# mcu.net
KiCad netlist of a schematic drawn in Altium Designer
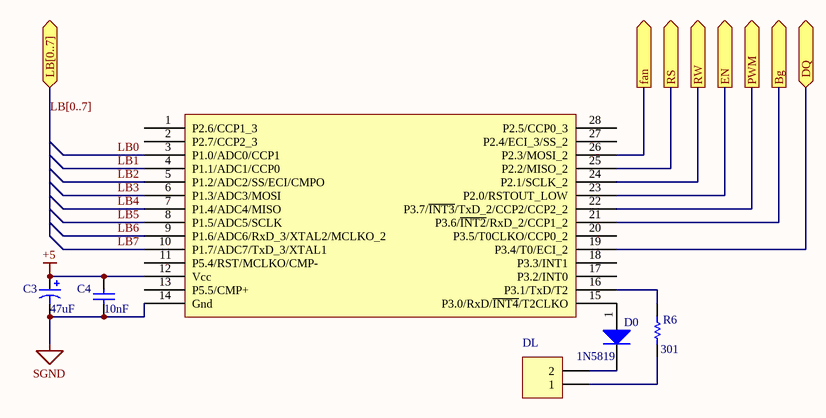
[diagram p0: mcu.SchDoc]

(export (version "E")
  (design (tool "Eeschema 10.0.6"))
  (components
    (comp (ref "C3")
      (value "47uF")
      (footprint "25V47uF(DIP)")
      (description "极性电容")
      (fields (field (name "Comment") "Cap1"))
      (libsource (lib "Self Establish") (part "Cap1"))
    )
    (comp (ref "C4")
      (value "10nF")
      (footprint "0805(M)")
      (description "非极性电容")
      (fields (field (name "Comment") "Cap2"))
      (libsource (lib "Self Establish") (part "Cap2"))
    )
    (comp (ref "D0")
      (value "1N5819")
      (footprint "SMA(M)")
      (description "肖特基二极管")
      (libsource (lib "Self Establish") (part "Diode2"))
    )
    (comp (ref "DL") (value "2Pin") (footprint "2Pin(DIP)") (libsource (lib "Self Establish") (part "2Pin")))
    (comp (ref "R6")
      (value "301")
      (footprint "0805(M)")
      (fields (field (name "Comment") "Res"))
      (libsource (lib "Self Establish") (part "Res"))
    )
    (comp (ref "U0")
      (value "STC15W401AS_SOP28_TSSOP28_SKDIP28")
      (footprint "SOP28")
      (libsource (lib "Self Establish") (part "STC15W401AS_SOP28_TSSOP28_SKDIP28"))
    )
  )
  (nets
    (net (code "1") (name "+5") (class "Default")
      (node (ref "C3") (pin "1") (pinfunction "1_1") (pintype "passive"))
      (node (ref "C4") (pin "2") (pinfunction "2_2") (pintype "passive"))
      (node (ref "U0") (pin "12") (pinfunction "Vcc_12") (pintype "passive"))
    )
    (net (code "2") (name "/Bg") (class "Default")
      (node (ref "U0") (pin "21") (pinfunction "P3.6/~{INT2}/RxD_2/CCP1_2_21") (pintype "passive"))
    )
    (net (code "3") (name "/DQ") (class "Default")
      (node (ref "U0") (pin "19") (pinfunction "P3.4/T0/ECI_2_19") (pintype "passive"))
    )
    (net (code "4") (name "/EN") (class "Default")
      (node (ref "U0") (pin "23") (pinfunction "P2.0/RSTOUT_LOW_23") (pintype "passive"))
    )
    (net (code "5") (name "/LB0") (class "Default")
      (node (ref "U0") (pin "3") (pinfunction "P1.0/ADC0/CCP1_3") (pintype "passive"))
    )
    (net (code "6") (name "/LB1") (class "Default")
      (node (ref "U0") (pin "4") (pinfunction "P1.1/ADC1/CCP0_4") (pintype "passive"))
    )
    (net (code "7") (name "/LB2") (class "Default")
      (node (ref "U0") (pin "5") (pinfunction "P1.2/ADC2/SS/ECI/CMPO_5") (pintype "passive"))
    )
    (net (code "8") (name "/LB3") (class "Default")
      (node (ref "U0") (pin "6") (pinfunction "P1.3/ADC3/MOSI_6") (pintype "passive"))
    )
    (net (code "9") (name "/LB4") (class "Default")
      (node (ref "U0") (pin "7") (pinfunction "P1.4/ADC4/MISO_7") (pintype "passive"))
    )
    (net (code "10") (name "/LB5") (class "Default")
      (node (ref "U0") (pin "8") (pinfunction "P1.5/ADC5/SCLK_8") (pintype "passive"))
    )
    (net (code "11") (name "/LB6") (class "Default")
      (node (ref "U0") (pin "9") (pinfunction "P1.6/ADC6/RxD_3/XTAL2/MCLKO_2_9") (pintype "passive"))
    )
    (net (code "12") (name "/LB7") (class "Default")
      (node (ref "U0") (pin "10") (pinfunction "P1.7/ADC7/TxD_3/XTAL1_10") (pintype "passive"))
    )
    (net (code "14") (name "/PWM") (class "Default")
      (node (ref "U0") (pin "22") (pinfunction "P3.7/~{INT3}/TxD_2/CCP2/CCP2_2_22") (pintype "passive"))
    )
    (net (code "15") (name "/RS") (class "Default")
      (node (ref "U0") (pin "25") (pinfunction "P2.2/MISO_2_25") (pintype "passive"))
    )
    (net (code "16") (name "/RW") (class "Default")
      (node (ref "U0") (pin "24") (pinfunction "P2.1/SCLK_2_24") (pintype "passive"))
    )
    (net (code "17") (name "/fan") (class "Default")
      (node (ref "U0") (pin "26") (pinfunction "P2.3/MOSI_2_26") (pintype "passive"))
    )
    (net (code "18") (name "Net-(D0-N)") (class "Default")
      (node (ref "D0") (pin "2") (pinfunction "N_2") (pintype "passive"))
      (node (ref "DL") (pin "2") (pinfunction "2_2") (pintype "passive"))
    )
    (net (code "19") (name "Net-(D0-P)") (class "Default")
      (node (ref "D0") (pin "1") (pinfunction "P_1") (pintype "passive"))
      (node (ref "U0") (pin "15") (pinfunction "P3.0/RxD/~{INT4}/T2CLKO_15") (pintype "passive"))
    )
    (net (code "20") (name "Net-(DL-Pad1)") (class "Default")
      (node (ref "DL") (pin "1") (pinfunction "1_1") (pintype "passive"))
      (node (ref "R6") (pin "2") (pinfunction "2_2") (pintype "passive"))
    )
    (net (code "21") (name "Net-(U0-P3.1{slash}TxD{slash}T2)") (class "Default")
      (node (ref "R6") (pin "1") (pinfunction "1_1") (pintype "passive"))
      (node (ref "U0") (pin "16") (pinfunction "P3.1/TxD/T2_16") (pintype "passive"))
    )
    (net (code "22") (name "SGND") (class "Default")
      (node (ref "C3") (pin "2") (pinfunction "2_2") (pintype "passive"))
      (node (ref "C4") (pin "1") (pinfunction "1_1") (pintype "passive"))
      (node (ref "U0") (pin "14") (pinfunction "Gnd_14") (pintype "passive"))
    )
    (net (code "23") (name "unconnected-(U0-P2.4{slash}ECI_3{slash}SS_2-Pad27)") (class "Default")
      (node (ref "U0") (pin "27") (pinfunction "P2.4/ECI_3/SS_2_27") (pintype "passive"))
    )
    (net (code "24") (name "unconnected-(U0-P2.5{slash}CCP0_3-Pad28)") (class "Default")
      (node (ref "U0") (pin "28") (pinfunction "P2.5/CCP0_3_28") (pintype "passive"))
    )
    (net (code "25") (name "unconnected-(U0-P2.6{slash}CCP1_3-Pad1)") (class "Default")
      (node (ref "U0") (pin "1") (pinfunction "P2.6/CCP1_3_1") (pintype "passive"))
    )
    (net (code "26") (name "unconnected-(U0-P2.7{slash}CCP2_3-Pad2)") (class "Default")
      (node (ref "U0") (pin "2") (pinfunction "P2.7/CCP2_3_2") (pintype "passive"))
    )
    (net (code "27") (name "unconnected-(U0-P3.2{slash}INT0-Pad17)") (class "Default")
      (node (ref "U0") (pin "17") (pinfunction "P3.2/INT0_17") (pintype "passive"))
    )
    (net (code "28") (name "unconnected-(U0-P3.3{slash}INT1-Pad18)") (class "Default")
      (node (ref "U0") (pin "18") (pinfunction "P3.3/INT1_18") (pintype "passive"))
    )
    (net (code "29") (name "unconnected-(U0-P3.5{slash}T0CLKO{slash}CCP0_2-Pad20)") (class "Default")
      (node (ref "U0") (pin "20") (pinfunction "P3.5/T0CLKO/CCP0_2_20") (pintype "passive"))
    )
    (net (code "30") (name "unconnected-(U0-P5.4{slash}RST{slash}MCLKO{slash}CMP--Pad11)") (class "Default")
      (node (ref "U0") (pin "11") (pinfunction "P5.4/RST/MCLKO/CMP-_11") (pintype "passive"))
    )
    (net (code "31") (name "unconnected-(U0-P5.5{slash}CMP+-Pad13)") (class "Default")
      (node (ref "U0") (pin "13") (pinfunction "P5.5/CMP+_13") (pintype "passive"))
    )
  )
)
